# PICO.net
KiCad netlist of a schematic drawn in Altium Designer
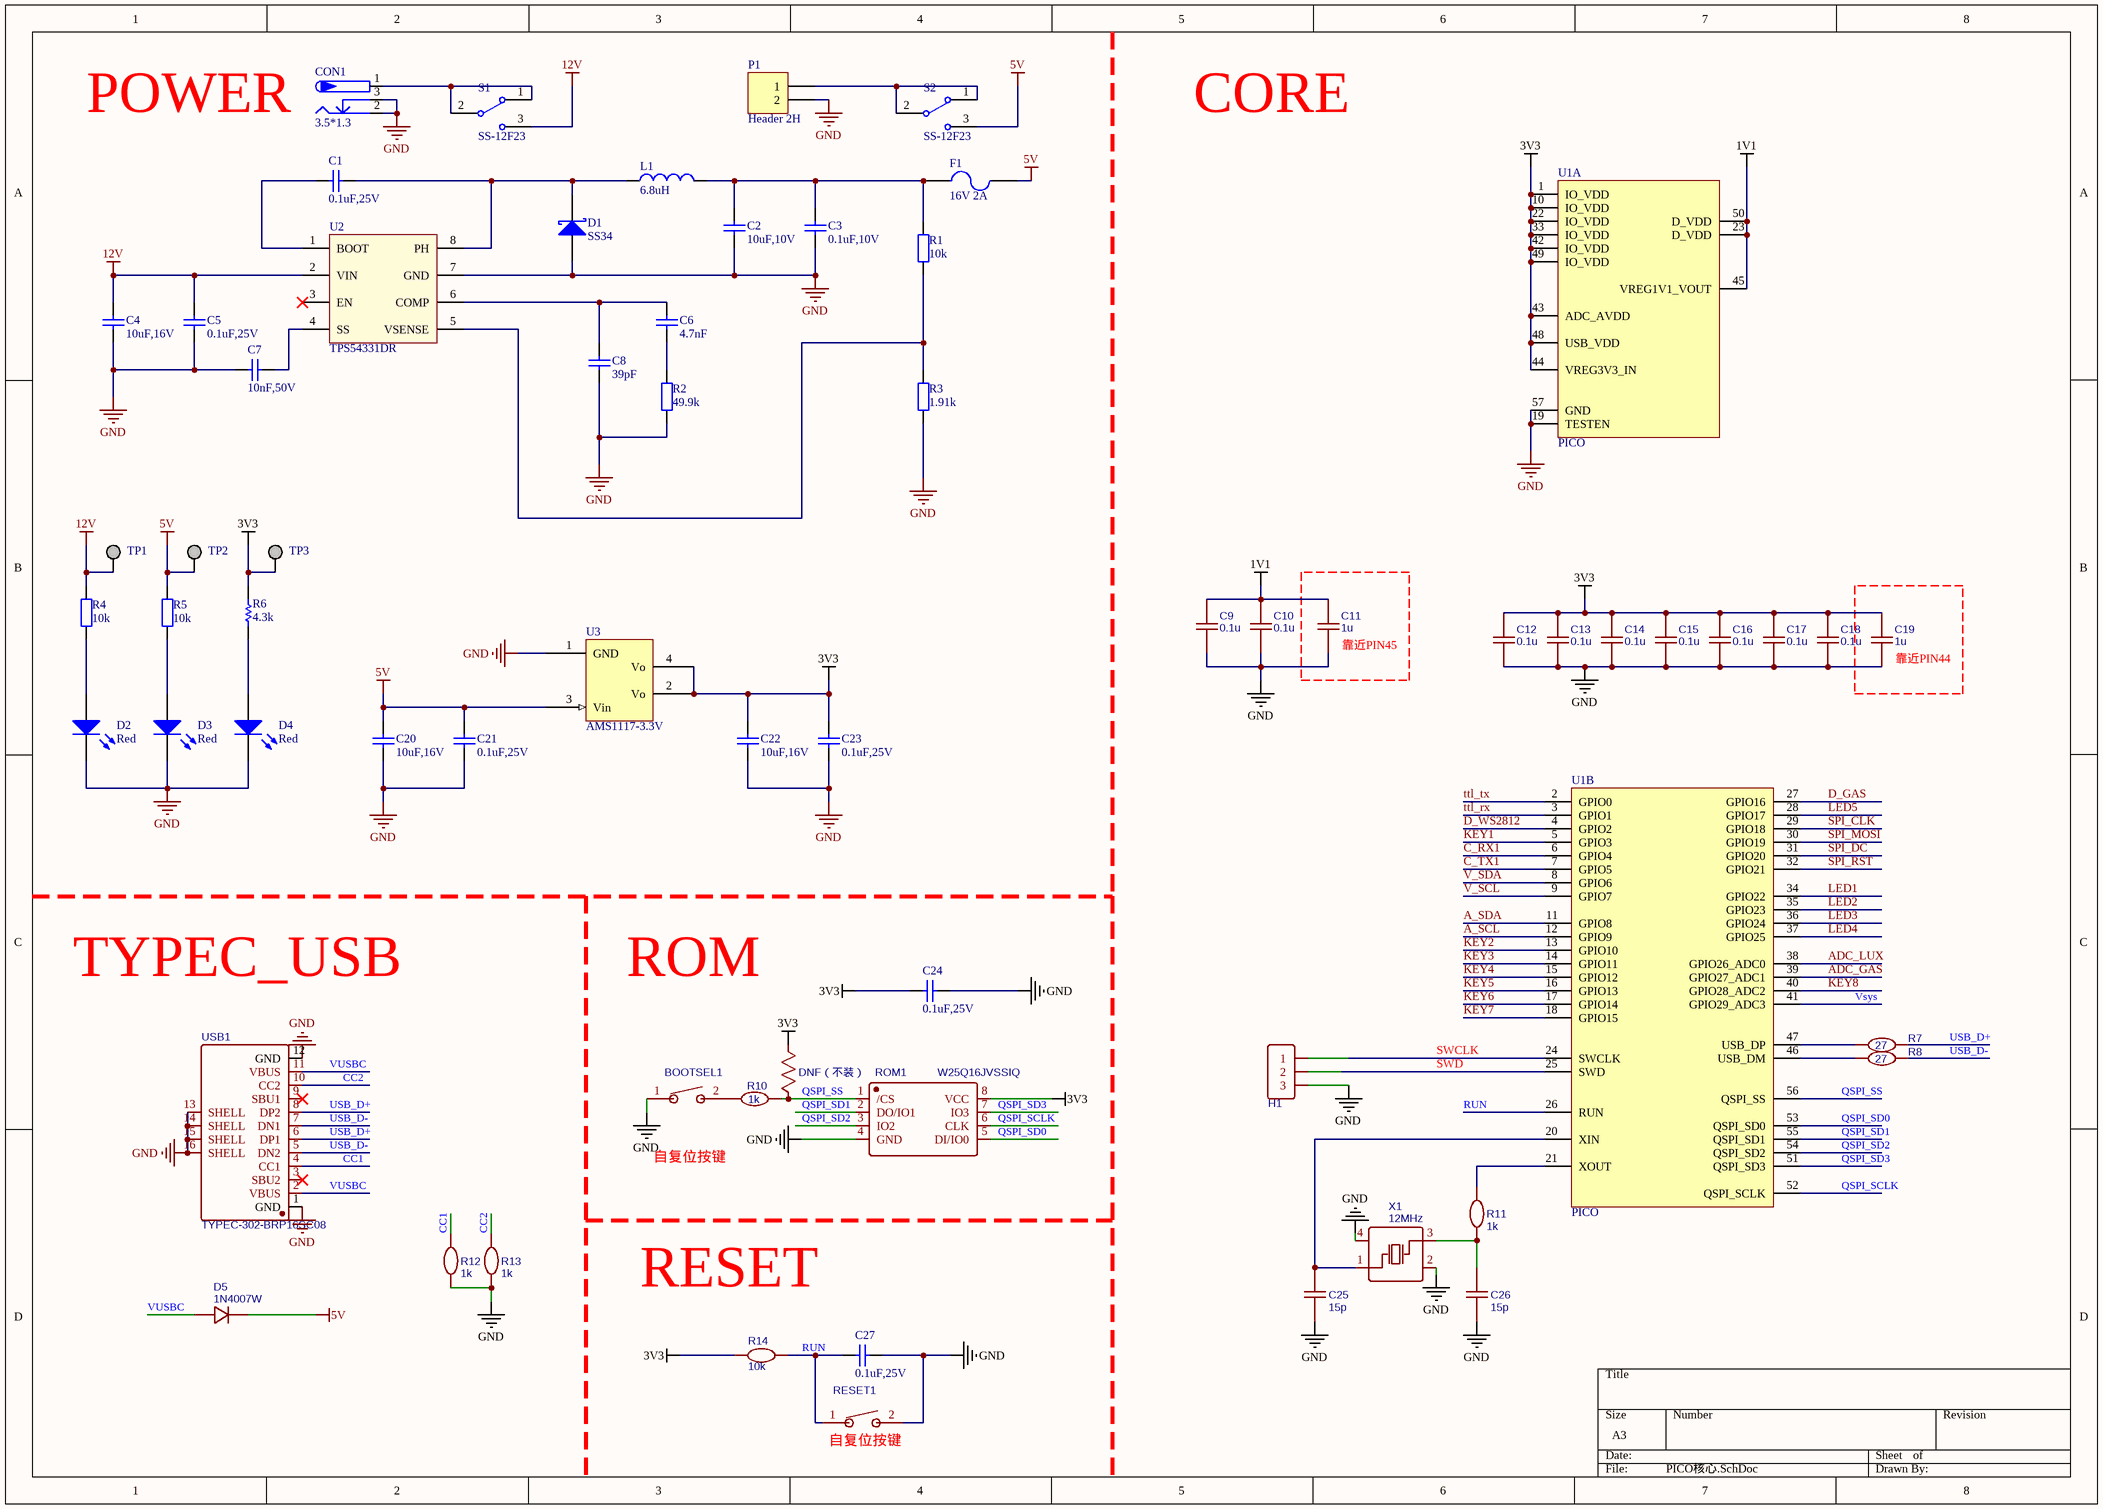
[diagram p0: PICO核心.SchDoc]

(export (version "E")
  (design (tool "Eeschema 10.0.6"))
  (components
    (comp (ref "BOOTSEL1")
      (value "TSA343G00-250J2")
      (footprint "SW-SMD_4P-L6.2-W6.3-P4.00-LS9.4")
      (fields (field (name "BOM_SUPPLIER PART") "C354946") (field (name "CONTRIBUTOR") "LCSC"))
      (libsource (lib "altium-import") (part "root_0_TSA343G00-250J2_"))
    )
    (comp (ref "C1")
      (value "0.1uF,25V")
      (footprint "0402_C")
      (description "贴片电容")
      (fields (field (name "PART NUMBER") "T_Cap_0603_0.1uF_25V_X5R") (field (name "TOLERANCE") "10%"))
      (libsource (lib "Database_Library") (part "Cap"))
    )
    (comp (ref "C2")
      (value "10uF,10V")
      (footprint "0402_C")
      (description "贴片电容")
      (fields (field (name "PART NUMBER") "T_Cap_1206_47uF_10V_X5R") (field (name "TOLERANCE") "10%"))
      (libsource (lib "Database_Library") (part "Cap"))
    )
    (comp (ref "C3")
      (value "0.1uF,10V")
      (footprint "1206_C")
      (description "贴片电容")
      (fields (field (name "PART NUMBER") "T_Cap_1206_47uF_10V_X5R") (field (name "TOLERANCE") "10%"))
      (libsource (lib "Database_Library") (part "Cap"))
    )
    (comp (ref "C4")
      (value "10uF,16V")
      (footprint "0402_C")
      (description "贴片电容")
      (fields (field (name "PART NUMBER") "T_Cap_0603_10uF_16V_X5R") (field (name "TOLERANCE") "10%"))
      (libsource (lib "Database_Library") (part "Cap"))
    )
    (comp (ref "C5")
      (value "0.1uF,25V")
      (footprint "0402_C")
      (description "贴片电容")
      (fields (field (name "PART NUMBER") "T_Cap_0603_0.1uF_25V_X5R") (field (name "TOLERANCE") "10%"))
      (libsource (lib "Database_Library") (part "Cap"))
    )
    (comp (ref "C6") (value "4.7nF") (footprint "0402_C") (libsource (lib "MyLibrary") (part "Cap")))
    (comp (ref "C7")
      (value "10nF,50V")
      (footprint "0402_C")
      (description "贴片电容")
      (fields (field (name "PART NUMBER") "T_Cap_0603_10nF_50V_X7R") (field (name "TOLERANCE") "10%"))
      (libsource (lib "Database_Library") (part "Cap"))
    )
    (comp (ref "C8") (value "39pF") (footprint "0402_C") (libsource (lib "MyLibrary") (part "Cap")))
    (comp (ref "C9")
      (value "0.1u")
      (footprint "0402_C")
      (fields (field (name "CONTRIBUTOR") "LCEDA_Lib"))
      (libsource (lib "altium-import") (part "root_3_0.1u_"))
    )
    (comp (ref "C10")
      (value "0.1u")
      (footprint "0402_C")
      (fields (field (name "CONTRIBUTOR") "LCEDA_Lib"))
      (libsource (lib "altium-import") (part "root_3_0.1u_"))
    )
    (comp (ref "C11")
      (value "1u")
      (footprint "0402_C")
      (fields (field (name "CONTRIBUTOR") "LCEDA_Lib"))
      (libsource (lib "altium-import") (part "root_1_0.1u_"))
    )
    (comp (ref "C12")
      (value "0.1u")
      (footprint "0402_C")
      (fields (field (name "CONTRIBUTOR") "LCEDA_Lib"))
      (libsource (lib "altium-import") (part "root_3_0.1u_"))
    )
    (comp (ref "C13")
      (value "0.1u")
      (footprint "0402_C")
      (fields (field (name "CONTRIBUTOR") "LCEDA_Lib"))
      (libsource (lib "altium-import") (part "root_1_0.1u_"))
    )
    (comp (ref "C14")
      (value "0.1u")
      (footprint "0402_C")
      (fields (field (name "CONTRIBUTOR") "LCEDA_Lib"))
      (libsource (lib "altium-import") (part "root_1_0.1u_"))
    )
    (comp (ref "C15")
      (value "0.1u")
      (footprint "0402_C")
      (fields (field (name "CONTRIBUTOR") "LCEDA_Lib"))
      (libsource (lib "altium-import") (part "root_1_0.1u_"))
    )
    (comp (ref "C16")
      (value "0.1u")
      (footprint "0402_C")
      (fields (field (name "CONTRIBUTOR") "LCEDA_Lib"))
      (libsource (lib "altium-import") (part "root_1_0.1u_"))
    )
    (comp (ref "C17")
      (value "0.1u")
      (footprint "0402_C")
      (fields (field (name "CONTRIBUTOR") "LCEDA_Lib"))
      (libsource (lib "altium-import") (part "root_1_0.1u_"))
    )
    (comp (ref "C18")
      (value "0.1u")
      (footprint "0402_C")
      (fields (field (name "CONTRIBUTOR") "LCEDA_Lib"))
      (libsource (lib "altium-import") (part "root_1_0.1u_"))
    )
    (comp (ref "C19")
      (value "1u")
      (footprint "0402_C")
      (fields (field (name "CONTRIBUTOR") "LCEDA_Lib"))
      (libsource (lib "altium-import") (part "root_1_0.1u_"))
    )
    (comp (ref "C20")
      (value "10uF,16V")
      (footprint "0402_C")
      (description "贴片电容")
      (fields (field (name "PART NUMBER") "T_Cap_0603_10uF_16V_X5R") (field (name "TOLERANCE") "10%"))
      (libsource (lib "Database_Library") (part "Cap"))
    )
    (comp (ref "C21")
      (value "0.1uF,25V")
      (footprint "0402_C")
      (description "贴片电容")
      (fields (field (name "PART NUMBER") "T_Cap_0603_0.1uF_25V_X5R") (field (name "TOLERANCE") "10%"))
      (libsource (lib "Database_Library") (part "Cap"))
    )
    (comp (ref "C22")
      (value "10uF,16V")
      (footprint "0402_C")
      (description "贴片电容")
      (fields (field (name "PART NUMBER") "T_Cap_0603_10uF_16V_X5R") (field (name "TOLERANCE") "10%"))
      (libsource (lib "Database_Library") (part "Cap"))
    )
    (comp (ref "C23")
      (value "0.1uF,25V")
      (footprint "0402_C")
      (description "贴片电容")
      (fields (field (name "PART NUMBER") "T_Cap_0603_0.1uF_25V_X5R") (field (name "TOLERANCE") "10%"))
      (libsource (lib "Database_Library") (part "Cap"))
    )
    (comp (ref "C24")
      (value "0.1uF,25V")
      (footprint "0402_C")
      (description "贴片电容")
      (fields (field (name "PART NUMBER") "T_Cap_0603_0.1uF_25V_X5R") (field (name "TOLERANCE") "10%"))
      (libsource (lib "Database_Library") (part "Cap"))
    )
    (comp (ref "C25")
      (value "15p")
      (footprint "0402_C")
      (fields (field (name "CONTRIBUTOR") "LCEDA_Lib"))
      (libsource (lib "altium-import") (part "root_1_15p_"))
    )
    (comp (ref "C26")
      (value "15p")
      (footprint "0402_C")
      (fields (field (name "CONTRIBUTOR") "LCEDA_Lib"))
      (libsource (lib "altium-import") (part "root_1_15p_"))
    )
    (comp (ref "C27")
      (value "0.1uF,25V")
      (footprint "0402_C")
      (description "贴片电容")
      (fields (field (name "PART NUMBER") "T_Cap_0603_0.1uF_25V_X5R") (field (name "TOLERANCE") "10%"))
      (libsource (lib "Database_Library") (part "Cap"))
    )
    (comp (ref "CON1")
      (value "3.5*1.3")
      (footprint "DC-IN-TH_DC-005-5A-2.5")
      (description "低压电源接口")
      (fields (field (name "版权归属") "源创客"))
      (libsource (lib "Schlib_PICO") (part "P-DC"))
    )
    (comp (ref "D1")
      (value "SS34")
      (footprint "SMA_L4.3-W2.6-LS5.2-RD")
      (description "肖特基二极管")
      (fields (field (name "PART NUMBER") "T_SS34"))
      (libsource (lib "Database_Library") (part "Diode Schottky"))
    )
    (comp (ref "D2")
      (value "Red")
      (footprint "0603_LED")
      (description "红色LED灯")
      (fields (field (name "PART NUMBER") "T_LED_Red_0805"))
      (libsource (lib "Database_Library") (part "LED"))
    )
    (comp (ref "D3")
      (value "Red")
      (footprint "0603_LED")
      (description "红色LED灯")
      (fields (field (name "PART NUMBER") "T_LED_Red_0805"))
      (libsource (lib "Database_Library") (part "LED"))
    )
    (comp (ref "D4")
      (value "Red")
      (footprint "0603_LED")
      (description "红色LED灯")
      (fields (field (name "PART NUMBER") "T_LED_Red_0805"))
      (libsource (lib "Database_Library") (part "LED"))
    )
    (comp (ref "D5")
      (value "1N4007W")
      (footprint "SMA_L4.3-W2.6-LS5.2-RD")
      (fields (field (name "BOM_SUPPLIER PART") "C328592") (field (name "CONTRIBUTOR") "LCEDA_Lib"))
      (libsource (lib "altium-import") (part "root_0_1N4007W_"))
    )
    (comp (ref "F1") (value "16V 2A") (footprint "1206_FUSE") (libsource (lib "MyLibrary") (part "Fuse")))
    (comp (ref "H1")
      (value "HDR-F-2.54_1x3")
      (footprint "XH2.54A-3")
      (fields (field (name "BOM_SUPPLIER PART") "C146690") (field (name "CONTRIBUTOR") "LCEDA_Lib"))
      (libsource (lib "altium-import") (part "root_0_mirrored_HDR-F-2.54_1x3_"))
    )
    (comp (ref "L1")
      (value "6.8uH")
      (footprint "IND-SMD_L5.8-W5.2")
      (libsource (lib "MyLibrary") (part "Inductor"))
    )
    (comp (ref "P1")
      (value "Header 2H")
      (footprint "XH2.54A-2")
      (description "Header, 2-Pin, Right Angle")
      (fields (field (name "PUBLISHER") "Altium Limited"))
      (libsource (lib "Miscellaneous Connectors") (part "Header 2H"))
    )
    (comp (ref "R1")
      (value "10k")
      (footprint "0402_R")
      (description "贴片电阻")
      (fields (field (name "PART NUMBER") "T_Res_0603_10k_1%_1/10W") (field (name "POWER") "1/10W"))
      (libsource (lib "Database_Library") (part "Res"))
    )
    (comp (ref "R2") (value "49.9k") (footprint "0402_R") (libsource (lib "MyLibrary") (part "Res")))
    (comp (ref "R3") (value "1.91k") (footprint "0402_R") (libsource (lib "MyLibrary") (part "Res")))
    (comp (ref "R4")
      (value "10k")
      (footprint "0402_R")
      (description "贴片电阻")
      (fields (field (name "PART NUMBER") "T_Res_0603_10k_1%_1/10W") (field (name "POWER") "1/10W"))
      (libsource (lib "Database_Library") (part "Res"))
    )
    (comp (ref "R5")
      (value "10k")
      (footprint "0402_R")
      (description "贴片电阻")
      (fields (field (name "PART NUMBER") "T_Res_0603_10k_1%_1/10W") (field (name "POWER") "1/10W"))
      (libsource (lib "Database_Library") (part "Res"))
    )
    (comp (ref "R6")
      (value "4.3k")
      (footprint "0402_R")
      (description "贴片电阻")
      (fields (field (name "PART NUMBER") "T_Res_0603_4.3k_5%_1/10W") (field (name "POWER") "1/10W"))
      (libsource (lib "Database_Library") (part "Res_5%"))
    )
    (comp (ref "R7")
      (value "27")
      (footprint "0402_R")
      (fields (field (name "CONTRIBUTOR") "LCEDA_Lib"))
      (libsource (lib "altium-import") (part "root_0_27_"))
    )
    (comp (ref "R8")
      (value "27")
      (footprint "0402_R")
      (fields (field (name "CONTRIBUTOR") "LCEDA_Lib"))
      (libsource (lib "altium-import") (part "root_0_27_"))
    )
    (comp (ref "R9")
      (value "DNF（不装）")
      (footprint "0402_R")
      (fields (field (name "CONTRIBUTOR") "LCEDA_Lib"))
      (libsource (lib "altium-import") (part "root_1_DNF（不装）_"))
    )
    (comp (ref "R10")
      (value "1k")
      (footprint "0402_R")
      (fields (field (name "CONTRIBUTOR") "LCEDA_Lib"))
      (libsource (lib "altium-import") (part "root_0_1k_"))
    )
    (comp (ref "R11")
      (value "1k")
      (footprint "0402_R")
      (fields (field (name "CONTRIBUTOR") "LCEDA_Lib"))
      (libsource (lib "altium-import") (part "root_1_1k_"))
    )
    (comp (ref "R12")
      (value "1k")
      (footprint "0402_R")
      (fields (field (name "CONTRIBUTOR") "LCEDA_Lib"))
      (libsource (lib "altium-import") (part "root_1_1k_"))
    )
    (comp (ref "R13")
      (value "1k")
      (footprint "0402_R")
      (fields (field (name "CONTRIBUTOR") "LCEDA_Lib"))
      (libsource (lib "altium-import") (part "root_1_1k_"))
    )
    (comp (ref "R14")
      (value "10k")
      (footprint "0402_R")
      (fields (field (name "CONTRIBUTOR") "LCEDA_Lib"))
      (libsource (lib "altium-import") (part "root_2_1k_"))
    )
    (comp (ref "RESET1")
      (value "TSA343G00-250J2")
      (footprint "SW-SMD_4P-L6.2-W6.3-P4.00-LS9.4")
      (fields (field (name "BOM_SUPPLIER PART") "C354946") (field (name "CONTRIBUTOR") "LCSC"))
      (libsource (lib "altium-import") (part "root_0_TSA343G00-250J2_"))
    )
    (comp (ref "ROM1")
      (value "W25Q16JVSSIQ")
      (footprint "SOIC8-208mil")
      (fields (field (name "BOM_SUPPLIER PART") "C82317"))
      (libsource (lib "altium-import") (part "root_0_W25Q16JVSSIQ_"))
    )
    (comp (ref "S1")
      (value "SS-12F23")
      (footprint "SW-TH_MT-0-103-A101-M200-RS")
      (description "1路波动开关")
      (fields (field (name "版权归属") "源创客"))
      (libsource (lib "Schlib_PICO") (part "SSW-1P"))
    )
    (comp (ref "S2")
      (value "SS-12F23")
      (footprint "SW-TH_MT-0-103-A101-M200-RS")
      (description "1路波动开关")
      (fields (field (name "版权归属") "源创客"))
      (libsource (lib "Schlib_PICO") (part "SSW-1P"))
    )
    (comp (ref "TP1")
      (value "T_TestPoint_H")
      (footprint "TP_H")
      (description "测试点_过孔")
      (libsource (lib "Database_Library") (part "TP"))
    )
    (comp (ref "TP2")
      (value "T_TestPoint_H")
      (footprint "TP_H")
      (description "测试点_过孔")
      (libsource (lib "Database_Library") (part "TP"))
    )
    (comp (ref "TP3")
      (value "T_TestPoint_H")
      (footprint "TP_H")
      (description "测试点_过孔")
      (libsource (lib "Database_Library") (part "TP"))
    )
    (comp (ref "U1")
      (value "PICO")
      (footprint "LQFN-56_L7.0-W7.0-P0.4-EP")
      (libsource (lib "Schlib_PICO") (part "PICO_CORE"))
    )
    (comp (ref "U2")
      (value "TPS54331DR")
      (footprint "SOIC8E")
      (description "TI, 3A, 3.5-28V, Buck")
      (libsource (lib "MyLibrary") (part "TPS54331"))
    )
    (comp (ref "U3")
      (value "AMS1117-3.3V")
      (footprint "SOT223")
      (description "电源芯片")
      (fields (field (name "PART NUMBER") "T_AMS1117-3.3V"))
      (libsource (lib "Database_Library") (part "AMS1117"))
    )
    (comp (ref "USB1")
      (value "TYPEC-302-BRP16SC08")
      (footprint "USB-C-SMD_TYPEC-302-BRP16SC08")
      (fields (field (name "BOM_SUPPLIER PART") "C2835312") (field (name "CONTRIBUTOR") "LCSC"))
      (libsource (lib "altium-import") (part "root_2_TYPEC-302-BRP16SC08_"))
    )
    (comp (ref "X1")
      (value "12MHz")
      (footprint "OSC 3225-4P")
      (fields
        (field (name "BOM_MANUFACTURER PART") "X322512MLB4SI")
        (field (name "BOM_SUPPLIER PART") "C112971")
      )
      (libsource (lib "altium-import") (part "root_0_12MHz_"))
    )
  )
  (nets
    (net (code "1") (name "/ADC_GAS") (class "Default")
      (node (ref "U1") (pin "39") (pinfunction "GPIO27_ADC1_39") (pintype "passive"))
    )
    (net (code "2") (name "/ADC_LUX") (class "Default")
      (node (ref "U1") (pin "38") (pinfunction "GPIO26_ADC0_38") (pintype "passive"))
    )
    (net (code "3") (name "/A_SCL") (class "Default")
      (node (ref "U1") (pin "12") (pinfunction "GPIO9_12") (pintype "passive"))
    )
    (net (code "4") (name "/A_SDA") (class "Default")
      (node (ref "U1") (pin "11") (pinfunction "GPIO8_11") (pintype "passive"))
    )
    (net (code "5") (name "/CC1") (class "Default")
      (node (ref "R12") (pin "2") (pinfunction "2_2") (pintype "passive"))
      (node (ref "USB1") (pin "4") (pinfunction "CC1_4") (pintype "passive"))
    )
    (net (code "6") (name "/CC2") (class "Default")
      (node (ref "R13") (pin "2") (pinfunction "2_2") (pintype "passive"))
      (node (ref "USB1") (pin "10") (pinfunction "CC2_10") (pintype "passive"))
    )
    (net (code "7") (name "/C_RX1") (class "Default")
      (node (ref "U1") (pin "6") (pinfunction "GPIO4_6") (pintype "passive"))
    )
    (net (code "8") (name "/C_TX1") (class "Default")
      (node (ref "U1") (pin "7") (pinfunction "GPIO5_7") (pintype "passive"))
    )
    (net (code "9") (name "/D_GAS") (class "Default")
      (node (ref "U1") (pin "27") (pinfunction "GPIO16_27") (pintype "passive"))
    )
    (net (code "10") (name "/D_WS2812") (class "Default")
      (node (ref "U1") (pin "4") (pinfunction "GPIO2_4") (pintype "passive"))
    )
    (net (code "11") (name "/KEY1") (class "Default")
      (node (ref "U1") (pin "5") (pinfunction "GPIO3_5") (pintype "passive"))
    )
    (net (code "12") (name "/KEY2") (class "Default")
      (node (ref "U1") (pin "13") (pinfunction "GPIO10_13") (pintype "passive"))
    )
    (net (code "13") (name "/KEY3") (class "Default")
      (node (ref "U1") (pin "14") (pinfunction "GPIO11_14") (pintype "passive"))
    )
    (net (code "14") (name "/KEY4") (class "Default")
      (node (ref "U1") (pin "15") (pinfunction "GPIO12_15") (pintype "passive"))
    )
    (net (code "15") (name "/KEY5") (class "Default")
      (node (ref "U1") (pin "16") (pinfunction "GPIO13_16") (pintype "passive"))
    )
    (net (code "16") (name "/KEY6") (class "Default")
      (node (ref "U1") (pin "17") (pinfunction "GPIO14_17") (pintype "passive"))
    )
    (net (code "17") (name "/KEY7") (class "Default")
      (node (ref "U1") (pin "18") (pinfunction "GPIO15_18") (pintype "passive"))
    )
    (net (code "18") (name "/KEY8") (class "Default")
      (node (ref "U1") (pin "40") (pinfunction "GPIO28_ADC2_40") (pintype "passive"))
    )
    (net (code "19") (name "/LED1") (class "Default")
      (node (ref "U1") (pin "34") (pinfunction "GPIO22_34") (pintype "passive"))
    )
    (net (code "20") (name "/LED2") (class "Default")
      (node (ref "U1") (pin "35") (pinfunction "GPIO23_35") (pintype "passive"))
    )
    (net (code "21") (name "/LED3") (class "Default")
      (node (ref "U1") (pin "36") (pinfunction "GPIO24_36") (pintype "passive"))
    )
    (net (code "22") (name "/LED4") (class "Default")
      (node (ref "U1") (pin "37") (pinfunction "GPIO25_37") (pintype "passive"))
    )
    (net (code "23") (name "/LED5") (class "Default")
      (node (ref "U1") (pin "28") (pinfunction "GPIO17_28") (pintype "passive"))
    )
    (net (code "24") (name "/QSPI_SCLK") (class "Default")
      (node (ref "ROM1") (pin "6") (pinfunction "CLK_6") (pintype "passive"))
      (node (ref "U1") (pin "52") (pinfunction "QSPI_SCLK_52") (pintype "passive"))
    )
    (net (code "25") (name "/QSPI_SD0") (class "Default")
      (node (ref "ROM1") (pin "5") (pinfunction "DI/IO0_5") (pintype "passive"))
      (node (ref "U1") (pin "53") (pinfunction "QSPI_SD0_53") (pintype "passive"))
    )
    (net (code "26") (name "/QSPI_SD1") (class "Default")
      (node (ref "ROM1") (pin "2") (pinfunction "DO/IO1_2") (pintype "passive"))
      (node (ref "U1") (pin "55") (pinfunction "QSPI_SD1_55") (pintype "passive"))
    )
    (net (code "27") (name "/QSPI_SD2") (class "Default")
      (node (ref "ROM1") (pin "3") (pinfunction "IO2_3") (pintype "passive"))
      (node (ref "U1") (pin "54") (pinfunction "QSPI_SD2_54") (pintype "passive"))
    )
    (net (code "28") (name "/QSPI_SD3") (class "Default")
      (node (ref "ROM1") (pin "7") (pinfunction "IO3_7") (pintype "passive"))
      (node (ref "U1") (pin "51") (pinfunction "QSPI_SD3_51") (pintype "passive"))
    )
    (net (code "29") (name "/QSPI_SS") (class "Default")
      (node (ref "R10") (pin "2") (pinfunction "2_2") (pintype "passive"))
      (node (ref "R9") (pin "1") (pinfunction "1_1") (pintype "passive"))
      (node (ref "ROM1") (pin "1") (pinfunction "/CS_1") (pintype "passive"))
      (node (ref "U1") (pin "56") (pinfunction "QSPI_SS_56") (pintype "passive"))
    )
    (net (code "30") (name "/RUN") (class "Default")
      (node (ref "C27") (pin "1") (pinfunction "1_1") (pintype "passive"))
      (node (ref "R14") (pin "1") (pinfunction "1_1") (pintype "passive"))
      (node (ref "RESET1") (pin "1") (pinfunction "1_1") (pintype "passive"))
      (node (ref "U1") (pin "26") (pinfunction "RUN_26") (pintype "passive"))
    )
    (net (code "31") (name "/SPI_CLK") (class "Default")
      (node (ref "U1") (pin "29") (pinfunction "GPIO18_29") (pintype "passive"))
    )
    (net (code "32") (name "/SPI_DC") (class "Default")
      (node (ref "U1") (pin "31") (pinfunction "GPIO20_31") (pintype "passive"))
    )
    (net (code "33") (name "/SPI_MOSI") (class "Default")
      (node (ref "U1") (pin "30") (pinfunction "GPIO19_30") (pintype "passive"))
    )
    (net (code "34") (name "/SPI_RST") (class "Default")
      (node (ref "U1") (pin "32") (pinfunction "GPIO21_32") (pintype "passive"))
    )
    (net (code "35") (name "/USB_D+") (class "Default")
      (node (ref "R7") (pin "2") (pinfunction "2_2") (pintype "passive"))
      (node (ref "USB1") (pin "6") (pinfunction "DP1_6") (pintype "passive"))
      (node (ref "USB1") (pin "8") (pinfunction "DP2_8") (pintype "passive"))
    )
    (net (code "36") (name "/USB_D-") (class "Default")
      (node (ref "R8") (pin "2") (pinfunction "2_2") (pintype "passive"))
      (node (ref "USB1") (pin "5") (pinfunction "DN2_5") (pintype "passive"))
      (node (ref "USB1") (pin "7") (pinfunction "DN1_7") (pintype "passive"))
    )
    (net (code "37") (name "/VUSBC") (class "Default")
      (node (ref "D5") (pin "2") (pinfunction "2_2") (pintype "passive"))
      (node (ref "USB1") (pin "11") (pinfunction "VBUS_11") (pintype "passive"))
      (node (ref "USB1") (pin "2") (pinfunction "VBUS_2") (pintype "passive"))
    )
    (net (code "38") (name "/V_SCL") (class "Default")
      (node (ref "U1") (pin "9") (pinfunction "GPIO7_9") (pintype "passive"))
    )
    (net (code "39") (name "/V_SDA") (class "Default")
      (node (ref "U1") (pin "8") (pinfunction "GPIO6_8") (pintype "passive"))
    )
    (net (code "40") (name "/Vsys") (class "Default")
      (node (ref "U1") (pin "41") (pinfunction "GPIO29_ADC3_41") (pintype "passive"))
    )
    (net (code "41") (name "/ttl_rx") (class "Default")
      (node (ref "U1") (pin "3") (pinfunction "GPIO1_3") (pintype "passive"))
    )
    (net (code "42") (name "/ttl_tx") (class "Default")
      (node (ref "U1") (pin "2") (pinfunction "GPIO0_2") (pintype "passive"))
    )
    (net (code "43") (name "1V1") (class "Default")
      (node (ref "C10") (pin "1") (pinfunction "1_1") (pintype "passive"))
      (node (ref "C11") (pin "2") (pinfunction "2_2") (pintype "passive"))
      (node (ref "C9") (pin "1") (pinfunction "1_1") (pintype "passive"))
      (node (ref "U1") (pin "23") (pinfunction "D_VDD_23") (pintype "passive"))
      (node (ref "U1") (pin "45") (pinfunction "VREG1V1_VOUT_45") (pintype "passive"))
      (node (ref "U1") (pin "50") (pinfunction "D_VDD_50") (pintype "passive"))
    )
    (net (code "44") (name "3V3") (class "Default")
      (node (ref "C12") (pin "1") (pinfunction "1_1") (pintype "passive"))
      (node (ref "C13") (pin "2") (pinfunction "2_2") (pintype "passive"))
      (node (ref "C14") (pin "2") (pinfunction "2_2") (pintype "passive"))
      (node (ref "C15") (pin "2") (pinfunction "2_2") (pintype "passive"))
      (node (ref "C16") (pin "2") (pinfunction "2_2") (pintype "passive"))
      (node (ref "C17") (pin "2") (pinfunction "2_2") (pintype "passive"))
      (node (ref "C18") (pin "2") (pinfunction "2_2") (pintype "passive"))
      (node (ref "C19") (pin "2") (pinfunction "2_2") (pintype "passive"))
      (node (ref "C22") (pin "2") (pinfunction "2_2") (pintype "passive"))
      (node (ref "C23") (pin "2") (pinfunction "2_2") (pintype "passive"))
      (node (ref "C24") (pin "2") (pinfunction "2_2") (pintype "passive"))
      (node (ref "R14") (pin "2") (pinfunction "2_2") (pintype "passive"))
      (node (ref "R6") (pin "2") (pinfunction "2_2") (pintype "passive"))
      (node (ref "R9") (pin "2") (pinfunction "2_2") (pintype "passive"))
      (node (ref "ROM1") (pin "8") (pinfunction "VCC_8") (pintype "passive"))
      (node (ref "TP3") (pin "1") (pinfunction "1_1") (pintype "passive"))
      (node (ref "U1") (pin "1") (pinfunction "IO_VDD_1") (pintype "passive"))
      (node (ref "U1") (pin "10") (pinfunction "IO_VDD_10") (pintype "passive"))
      (node (ref "U1") (pin "22") (pinfunction "IO_VDD_22") (pintype "passive"))
      (node (ref "U1") (pin "33") (pinfunction "IO_VDD_33") (pintype "passive"))
      (node (ref "U1") (pin "42") (pinfunction "IO_VDD_42") (pintype "passive"))
      (node (ref "U1") (pin "43") (pinfunction "ADC_AVDD_43") (pintype "passive"))
      (node (ref "U1") (pin "44") (pinfunction "VREG3V3_IN_44") (pintype "passive"))
      (node (ref "U1") (pin "48") (pinfunction "USB_VDD_48") (pintype "passive"))
      (node (ref "U1") (pin "49") (pinfunction "IO_VDD_49") (pintype "passive"))
      (node (ref "U3") (pin "2") (pinfunction "Vo_2") (pintype "passive"))
      (node (ref "U3") (pin "4") (pinfunction "Vo_4") (pintype "passive"))
    )
    (net (code "45") (name "5V") (class "Default")
      (node (ref "C20") (pin "2") (pinfunction "2_2") (pintype "passive"))
      (node (ref "C21") (pin "2") (pinfunction "2_2") (pintype "passive"))
      (node (ref "D5") (pin "1") (pinfunction "1_1") (pintype "passive"))
      (node (ref "F1") (pin "2") (pinfunction "2_2") (pintype "passive"))
      (node (ref "R5") (pin "2") (pinfunction "2_2") (pintype "passive"))
      (node (ref "S2") (pin "3") (pinfunction "3_3") (pintype "passive"))
      (node (ref "TP2") (pin "1") (pinfunction "1_1") (pintype "passive"))
      (node (ref "U3") (pin "3") (pinfunction "Vin_3") (pintype "input"))
    )
    (net (code "46") (name "12V") (class "Default")
      (node (ref "C4") (pin "2") (pinfunction "2_2") (pintype "passive"))
      (node (ref "C5") (pin "2") (pinfunction "2_2") (pintype "passive"))
      (node (ref "R4") (pin "2") (pinfunction "2_2") (pintype "passive"))
      (node (ref "S1") (pin "3") (pinfunction "3_3") (pintype "passive"))
      (node (ref "TP1") (pin "1") (pinfunction "1_1") (pintype "passive"))
      (node (ref "U2") (pin "2") (pinfunction "VIN_2") (pintype "passive"))
    )
    (net (code "47") (name "GND") (class "Default")
      (node (ref "BOOTSEL1") (pin "1") (pinfunction "1_1") (pintype "passive"))
      (node (ref "C10") (pin "2") (pinfunction "2_2") (pintype "passive"))
      (node (ref "C11") (pin "1") (pinfunction "1_1") (pintype "passive"))
      (node (ref "C12") (pin "2") (pinfunction "2_2") (pintype "passive"))
      (node (ref "C13") (pin "1") (pinfunction "1_1") (pintype "passive"))
      (node (ref "C14") (pin "1") (pinfunction "1_1") (pintype "passive"))
      (node (ref "C15") (pin "1") (pinfunction "1_1") (pintype "passive"))
      (node (ref "C16") (pin "1") (pinfunction "1_1") (pintype "passive"))
      (node (ref "C17") (pin "1") (pinfunction "1_1") (pintype "passive"))
      (node (ref "C18") (pin "1") (pinfunction "1_1") (pintype "passive"))
      (node (ref "C19") (pin "1") (pinfunction "1_1") (pintype "passive"))
      (node (ref "C2") (pin "1") (pinfunction "1_1") (pintype "passive"))
      (node (ref "C20") (pin "1") (pinfunction "1_1") (pintype "passive"))
      (node (ref "C21") (pin "1") (pinfunction "1_1") (pintype "passive"))
      (node (ref "C22") (pin "1") (pinfunction "1_1") (pintype "passive"))
      (node (ref "C23") (pin "1") (pinfunction "1_1") (pintype "passive"))
      (node (ref "C24") (pin "1") (pinfunction "1_1") (pintype "passive"))
      (node (ref "C25") (pin "1") (pinfunction "1_1") (pintype "passive"))
      (node (ref "C26") (pin "1") (pinfunction "1_1") (pintype "passive"))
      (node (ref "C27") (pin "2") (pinfunction "2_2") (pintype "passive"))
      (node (ref "C3") (pin "1") (pinfunction "1_1") (pintype "passive"))
      (node (ref "C4") (pin "1") (pinfunction "1_1") (pintype "passive"))
      (node (ref "C5") (pin "1") (pinfunction "1_1") (pintype "passive"))
      (node (ref "C7") (pin "2") (pinfunction "2_2") (pintype "passive"))
      (node (ref "C8") (pin "1") (pinfunction "1_1") (pintype "passive"))
      (node (ref "C9") (pin "2") (pinfunction "2_2") (pintype "passive"))
      (node (ref "CON1") (pin "2") (pintype "power_in"))
      (node (ref "CON1") (pin "3") (pintype "power_in"))
      (node (ref "D1") (pin "1") (pinfunction "A_1") (pintype "passive"))
      (node (ref "D2") (pin "2") (pinfunction "K_2") (pintype "passive"))
      (node (ref "D3") (pin "2") (pinfunction "K_2") (pintype "passive"))
      (node (ref "D4") (pin "2") (pinfunction "K_2") (pintype "passive"))
      (node (ref "H1") (pin "3") (pinfunction "3_3") (pintype "passive"))
      (node (ref "P1") (pin "2") (pinfunction "2_2") (pintype "passive"))
      (node (ref "R12") (pin "1") (pinfunction "1_1") (pintype "passive"))
      (node (ref "R13") (pin "1") (pinfunction "1_1") (pintype "passive"))
      (node (ref "R2") (pin "1") (pinfunction "1_1") (pintype "passive"))
      (node (ref "R3") (pin "1") (pinfunction "1_1") (pintype "passive"))
      (node (ref "RESET1") (pin "2") (pinfunction "2_2") (pintype "passive"))
      (node (ref "ROM1") (pin "4") (pinfunction "GND_4") (pintype "passive"))
      (node (ref "U1") (pin "19") (pinfunction "TESTEN_19") (pintype "passive"))
      (node (ref "U1") (pin "57") (pinfunction "GND_57") (pintype "passive"))
      (node (ref "U2") (pin "7") (pinfunction "GND_7") (pintype "passive"))
      (node (ref "U3") (pin "1") (pinfunction "GND_1") (pintype "passive"))
      (node (ref "USB1") (pin "1") (pinfunction "GND_1") (pintype "passive"))
      (node (ref "USB1") (pin "12") (pinfunction "GND_12") (pintype "passive"))
      (node (ref "USB1") (pin "13") (pinfunction "SHELL_13") (pintype "passive"))
      (node (ref "USB1") (pin "14") (pinfunction "SHELL_14") (pintype "passive"))
      (node (ref "USB1") (pin "15") (pinfunction "SHELL_15") (pintype "passive"))
      (node (ref "USB1") (pin "16") (pinfunction "SHELL_16") (pintype "passive"))
      (node (ref "X1") (pin "2") (pinfunction "GND_2") (pintype "passive"))
      (node (ref "X1") (pin "4") (pinfunction "GND_4") (pintype "passive"))
    )
    (net (code "48") (name "Net-(BOOTSEL1-Pad2)") (class "Default")
      (node (ref "BOOTSEL1") (pin "2") (pinfunction "2_2") (pintype "passive"))
      (node (ref "R10") (pin "1") (pinfunction "1_1") (pintype "passive"))
    )
    (net (code "49") (name "Net-(C2-Pad2)") (class "Default")
      (node (ref "C2") (pin "2") (pinfunction "2_2") (pintype "passive"))
      (node (ref "C3") (pin "2") (pinfunction "2_2") (pintype "passive"))
      (node (ref "F1") (pin "1") (pinfunction "1_1") (pintype "passive"))
      (node (ref "L1") (pin "2") (pinfunction "2_2") (pintype "passive"))
      (node (ref "R1") (pin "2") (pinfunction "2_2") (pintype "passive"))
    )
    (net (code "50") (name "Net-(C6-Pad1)") (class "Default")
      (node (ref "C6") (pin "1") (pinfunction "1_1") (pintype "passive"))
      (node (ref "R2") (pin "2") (pinfunction "2_2") (pintype "passive"))
    )
    (net (code "51") (name "Net-(CON1-Pad1)") (class "Default")
      (node (ref "CON1") (pin "1") (pintype "power_in"))
      (node (ref "S1") (pin "1") (pinfunction "1_1") (pintype "passive"))
      (node (ref "S1") (pin "2") (pinfunction "2_2") (pintype "passive"))
    )
    (net (code "52") (name "Net-(D1-K)") (class "Default")
      (node (ref "C1") (pin "1") (pinfunction "1_1") (pintype "passive"))
      (node (ref "D1") (pin "2") (pinfunction "K_2") (pintype "passive"))
      (node (ref "L1") (pin "1") (pinfunction "1_1") (pintype "passive"))
      (node (ref "U2") (pin "8") (pinfunction "PH_8") (pintype "passive"))
    )
    (net (code "53") (name "Net-(D2-A)") (class "Default")
      (node (ref "D2") (pin "1") (pinfunction "A_1") (pintype "passive"))
      (node (ref "R4") (pin "1") (pinfunction "1_1") (pintype "passive"))
    )
    (net (code "54") (name "Net-(D3-A)") (class "Default")
      (node (ref "D3") (pin "1") (pinfunction "A_1") (pintype "passive"))
      (node (ref "R5") (pin "1") (pinfunction "1_1") (pintype "passive"))
    )
    (net (code "55") (name "Net-(D4-A)") (class "Default")
      (node (ref "D4") (pin "1") (pinfunction "A_1") (pintype "passive"))
      (node (ref "R6") (pin "1") (pinfunction "1_1") (pintype "passive"))
    )
    (net (code "56") (name "Net-(P1-Pad1)") (class "Default")
      (node (ref "P1") (pin "1") (pinfunction "1_1") (pintype "passive"))
      (node (ref "S2") (pin "1") (pinfunction "1_1") (pintype "passive"))
      (node (ref "S2") (pin "2") (pinfunction "2_2") (pintype "passive"))
    )
    (net (code "57") (name "Net-(U1B-SWCLK)") (class "Default")
      (node (ref "H1") (pin "1") (pinfunction "1_1") (pintype "passive"))
      (node (ref "U1") (pin "24") (pinfunction "SWCLK_24") (pintype "passive"))
    )
    (net (code "58") (name "Net-(U1B-SWD)") (class "Default")
      (node (ref "H1") (pin "2") (pinfunction "2_2") (pintype "passive"))
      (node (ref "U1") (pin "25") (pinfunction "SWD_25") (pintype "passive"))
    )
    (net (code "59") (name "Net-(U1B-USB_DM)") (class "Default")
      (node (ref "R8") (pin "1") (pinfunction "1_1") (pintype "passive"))
      (node (ref "U1") (pin "46") (pinfunction "USB_DM_46") (pintype "passive"))
    )
    (net (code "60") (name "Net-(U1B-USB_DP)") (class "Default")
      (node (ref "R7") (pin "1") (pinfunction "1_1") (pintype "passive"))
      (node (ref "U1") (pin "47") (pinfunction "USB_DP_47") (pintype "passive"))
    )
    (net (code "61") (name "Net-(U1B-XIN)") (class "Default")
      (node (ref "C25") (pin "2") (pinfunction "2_2") (pintype "passive"))
      (node (ref "U1") (pin "20") (pinfunction "XIN_20") (pintype "passive"))
      (node (ref "X1") (pin "1") (pinfunction "OSC1_1") (pintype "passive"))
    )
    (net (code "62") (name "Net-(U1B-XOUT)") (class "Default")
      (node (ref "R11") (pin "2") (pinfunction "2_2") (pintype "passive"))
      (node (ref "U1") (pin "21") (pinfunction "XOUT_21") (pintype "passive"))
    )
    (net (code "63") (name "Net-(U2-BOOT)") (class "Default")
      (node (ref "C1") (pin "2") (pinfunction "2_2") (pintype "passive"))
      (node (ref "U2") (pin "1") (pinfunction "BOOT_1") (pintype "passive"))
    )
    (net (code "64") (name "Net-(U2-COMP)") (class "Default")
      (node (ref "C6") (pin "2") (pinfunction "2_2") (pintype "passive"))
      (node (ref "C8") (pin "2") (pinfunction "2_2") (pintype "passive"))
      (node (ref "U2") (pin "6") (pinfunction "COMP_6") (pintype "passive"))
    )
    (net (code "65") (name "Net-(U2-SS)") (class "Default")
      (node (ref "C7") (pin "1") (pinfunction "1_1") (pintype "passive"))
      (node (ref "U2") (pin "4") (pinfunction "SS_4") (pintype "passive"))
    )
    (net (code "66") (name "Net-(U2-VSENSE)") (class "Default")
      (node (ref "R1") (pin "1") (pinfunction "1_1") (pintype "passive"))
      (node (ref "R3") (pin "2") (pinfunction "2_2") (pintype "passive"))
      (node (ref "U2") (pin "5") (pinfunction "VSENSE_5") (pintype "passive"))
    )
    (net (code "67") (name "Net-(X1-OSC2)") (class "Default")
      (node (ref "C26") (pin "2") (pinfunction "2_2") (pintype "passive"))
      (node (ref "R11") (pin "1") (pinfunction "1_1") (pintype "passive"))
      (node (ref "X1") (pin "3") (pinfunction "OSC2_3") (pintype "passive"))
    )
    (net (code "68") (name "unconnected-(U2-EN-Pad3)") (class "Default")
      (node (ref "U2") (pin "3") (pinfunction "EN_3") (pintype "passive+no_connect"))
    )
    (net (code "69") (name "unconnected-(USB1-SBU1-Pad9)") (class "Default")
      (node (ref "USB1") (pin "9") (pinfunction "SBU1_9") (pintype "passive+no_connect"))
    )
    (net (code "70") (name "unconnected-(USB1-SBU2-Pad3)") (class "Default")
      (node (ref "USB1") (pin "3") (pinfunction "SBU2_3") (pintype "passive+no_connect"))
    )
  )
)
